# Volant5_CAN_transceiver_1_0.net
KiCad netlist of a schematic drawn in Altium Designer
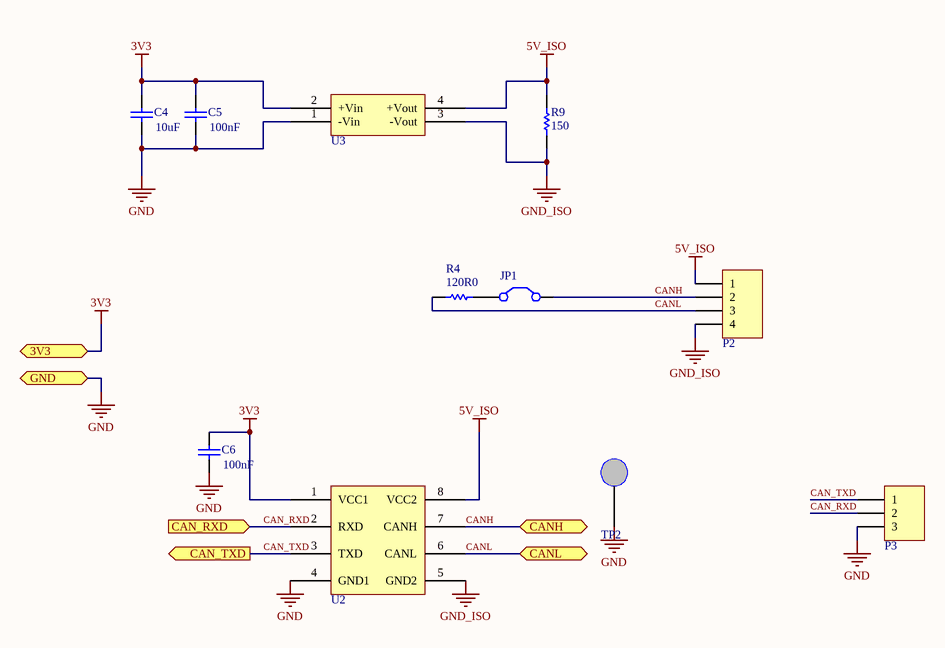
[diagram p0: Volant5.CAN_transceiver_1.0.SchDoc]

(export (version "E")
  (design (tool "Eeschema 10.0.6"))
  (components
    (comp (ref "C4")
      (value "10uF")
      (footprint "CS-0603")
      (fields (field (name "TOLERANCE") "10%") (field (name "Comment") "CS - CAPACITOR"))
      (libsource (lib "CHINOOK_LIBRARY") (part "CS - CAPACITOR"))
    )
    (comp (ref "C5")
      (value "100nF")
      (footprint "CS-0603")
      (fields (field (name "TOLERANCE") "10%") (field (name "Comment") "CS - CAPACITOR"))
      (libsource (lib "CHINOOK_LIBRARY") (part "CS - CAPACITOR"))
    )
    (comp (ref "C6")
      (value "100nF")
      (footprint "CS-0603")
      (fields (field (name "TOLERANCE") "10%") (field (name "Comment") "CS - CAPACITOR"))
      (libsource (lib "CHINOOK_LIBRARY") (part "CS - CAPACITOR"))
    )
    (comp (ref "JP1")
      (value "JMP - Jumper")
      (footprint "HEADER-2-JMP")
      (description "Jumper")
      (libsource (lib "CHINOOK_LIBRARY") (part "JMP - Jumper"))
    )
    (comp (ref "P2")
      (value "CON - HEADER 1X4")
      (footprint "CON-HEADER-1X4")
      (description "100mil header 1 row 4pins")
      (libsource (lib "CHINOOK_LIBRARY") (part "CON - HEADER 1X4"))
    )
    (comp (ref "P3")
      (value "CON - HEADER 1X3")
      (footprint "CON-HEADER-1X3")
      (description "100mil header 1 row 3pins")
      (libsource (lib "CHINOOK_LIBRARY") (part "CON - HEADER 1X3"))
    )
    (comp (ref "R4")
      (value "120R0")
      (footprint "RS-0603")
      (fields
        (field (name "TOLERANCE") "RES TOL")
        (field (name "POWER") "RES POWER")
        (field (name "Comment") "RS - RESISTOR")
      )
      (libsource (lib "CHINOOK_LIBRARY") (part "RS - RESISTOR"))
    )
    (comp (ref "R9")
      (value "150")
      (footprint "RS-0603")
      (fields
        (field (name "TOLERANCE") "RES TOL")
        (field (name "POWER") "RES POWER")
        (field (name "Comment") "RS - RESISTOR")
      )
      (libsource (lib "CHINOOK_LIBRARY") (part "RS - RESISTOR"))
    )
    (comp (ref "TP2")
      (value "5003K")
      (footprint "TP - VERTICAL")
      (libsource (lib "CHINOOK_LIBRARY") (part "TP - Test point vertical"))
    )
    (comp (ref "U2")
      (value "IC - ISO1050")
      (footprint "IC-SOP-8")
      (description "Isolated CAN transceiver")
      (fields (field (name "MANUFACTURER") "Texas Instrument"))
      (libsource (lib "CHINOOK_LIBRARY") (part "IC - ISO1050"))
    )
    (comp (ref "U3")
      (value "IC - CME0305S3C")
      (footprint "IC-SIP-4")
      (libsource (lib "CHINOOK_LIBRARY") (part "IC - CME0305S3C"))
    )
  )
  (nets
    (net (code "1") (name "/CANH") (class "Default")
      (node (ref "JP1") (pin "2") (pinfunction "C2_2") (pintype "passive"))
      (node (ref "P2") (pin "2") (pinfunction "2_2") (pintype "passive"))
      (node (ref "U2") (pin "7") (pinfunction "CANH_7") (pintype "passive"))
    )
    (net (code "2") (name "/CANL") (class "Default")
      (node (ref "P2") (pin "3") (pinfunction "3_3") (pintype "passive"))
      (node (ref "R4") (pin "2") (pinfunction "2_2") (pintype "passive"))
      (node (ref "U2") (pin "6") (pinfunction "CANL_6") (pintype "passive"))
    )
    (net (code "3") (name "/CAN_RXD") (class "Default")
      (node (ref "P3") (pin "2") (pinfunction "2_2") (pintype "passive"))
      (node (ref "U2") (pin "2") (pinfunction "RXD_2") (pintype "passive"))
    )
    (net (code "4") (name "/CAN_TXD") (class "Default")
      (node (ref "P3") (pin "1") (pinfunction "1_1") (pintype "passive"))
      (node (ref "U2") (pin "3") (pinfunction "TXD_3") (pintype "passive"))
    )
    (net (code "5") (name "3V3") (class "Default")
      (node (ref "C4") (pin "2") (pinfunction "2_2") (pintype "passive"))
      (node (ref "C5") (pin "2") (pinfunction "2_2") (pintype "passive"))
      (node (ref "C6") (pin "2") (pinfunction "2_2") (pintype "passive"))
      (node (ref "U2") (pin "1") (pinfunction "VCC1_1") (pintype "power_in"))
      (node (ref "U3") (pin "2") (pinfunction "+Vin_2") (pintype "passive"))
    )
    (net (code "6") (name "5V_ISO") (class "Default")
      (node (ref "P2") (pin "1") (pinfunction "1_1") (pintype "passive"))
      (node (ref "R9") (pin "2") (pinfunction "2_2") (pintype "passive"))
      (node (ref "U2") (pin "8") (pinfunction "VCC2_8") (pintype "passive"))
      (node (ref "U3") (pin "4") (pinfunction "+Vout_4") (pintype "passive"))
    )
    (net (code "7") (name "GND") (class "Default")
      (node (ref "C4") (pin "1") (pinfunction "1_1") (pintype "passive"))
      (node (ref "C5") (pin "1") (pinfunction "1_1") (pintype "passive"))
      (node (ref "C6") (pin "1") (pinfunction "1_1") (pintype "passive"))
      (node (ref "P3") (pin "3") (pinfunction "3_3") (pintype "passive"))
      (node (ref "TP2") (pin "1") (pinfunction "1_1") (pintype "passive"))
      (node (ref "U2") (pin "4") (pinfunction "GND1_4") (pintype "passive"))
      (node (ref "U3") (pin "1") (pinfunction "-Vin_1") (pintype "passive"))
    )
    (net (code "8") (name "GND_ISO") (class "Default")
      (node (ref "P2") (pin "4") (pinfunction "4_4") (pintype "passive"))
      (node (ref "R9") (pin "1") (pinfunction "1_1") (pintype "passive"))
      (node (ref "U2") (pin "5") (pinfunction "GND2_5") (pintype "passive"))
      (node (ref "U3") (pin "3") (pinfunction "-Vout_3") (pintype "passive"))
    )
    (net (code "9") (name "Net-(JP1-C1)") (class "Default")
      (node (ref "JP1") (pin "1") (pinfunction "C1_1") (pintype "passive"))
      (node (ref "R4") (pin "1") (pinfunction "1_1") (pintype "passive"))
    )
  )
)
